# IntegratedSensor.net
KiCad netlist of a schematic drawn in EAGLE
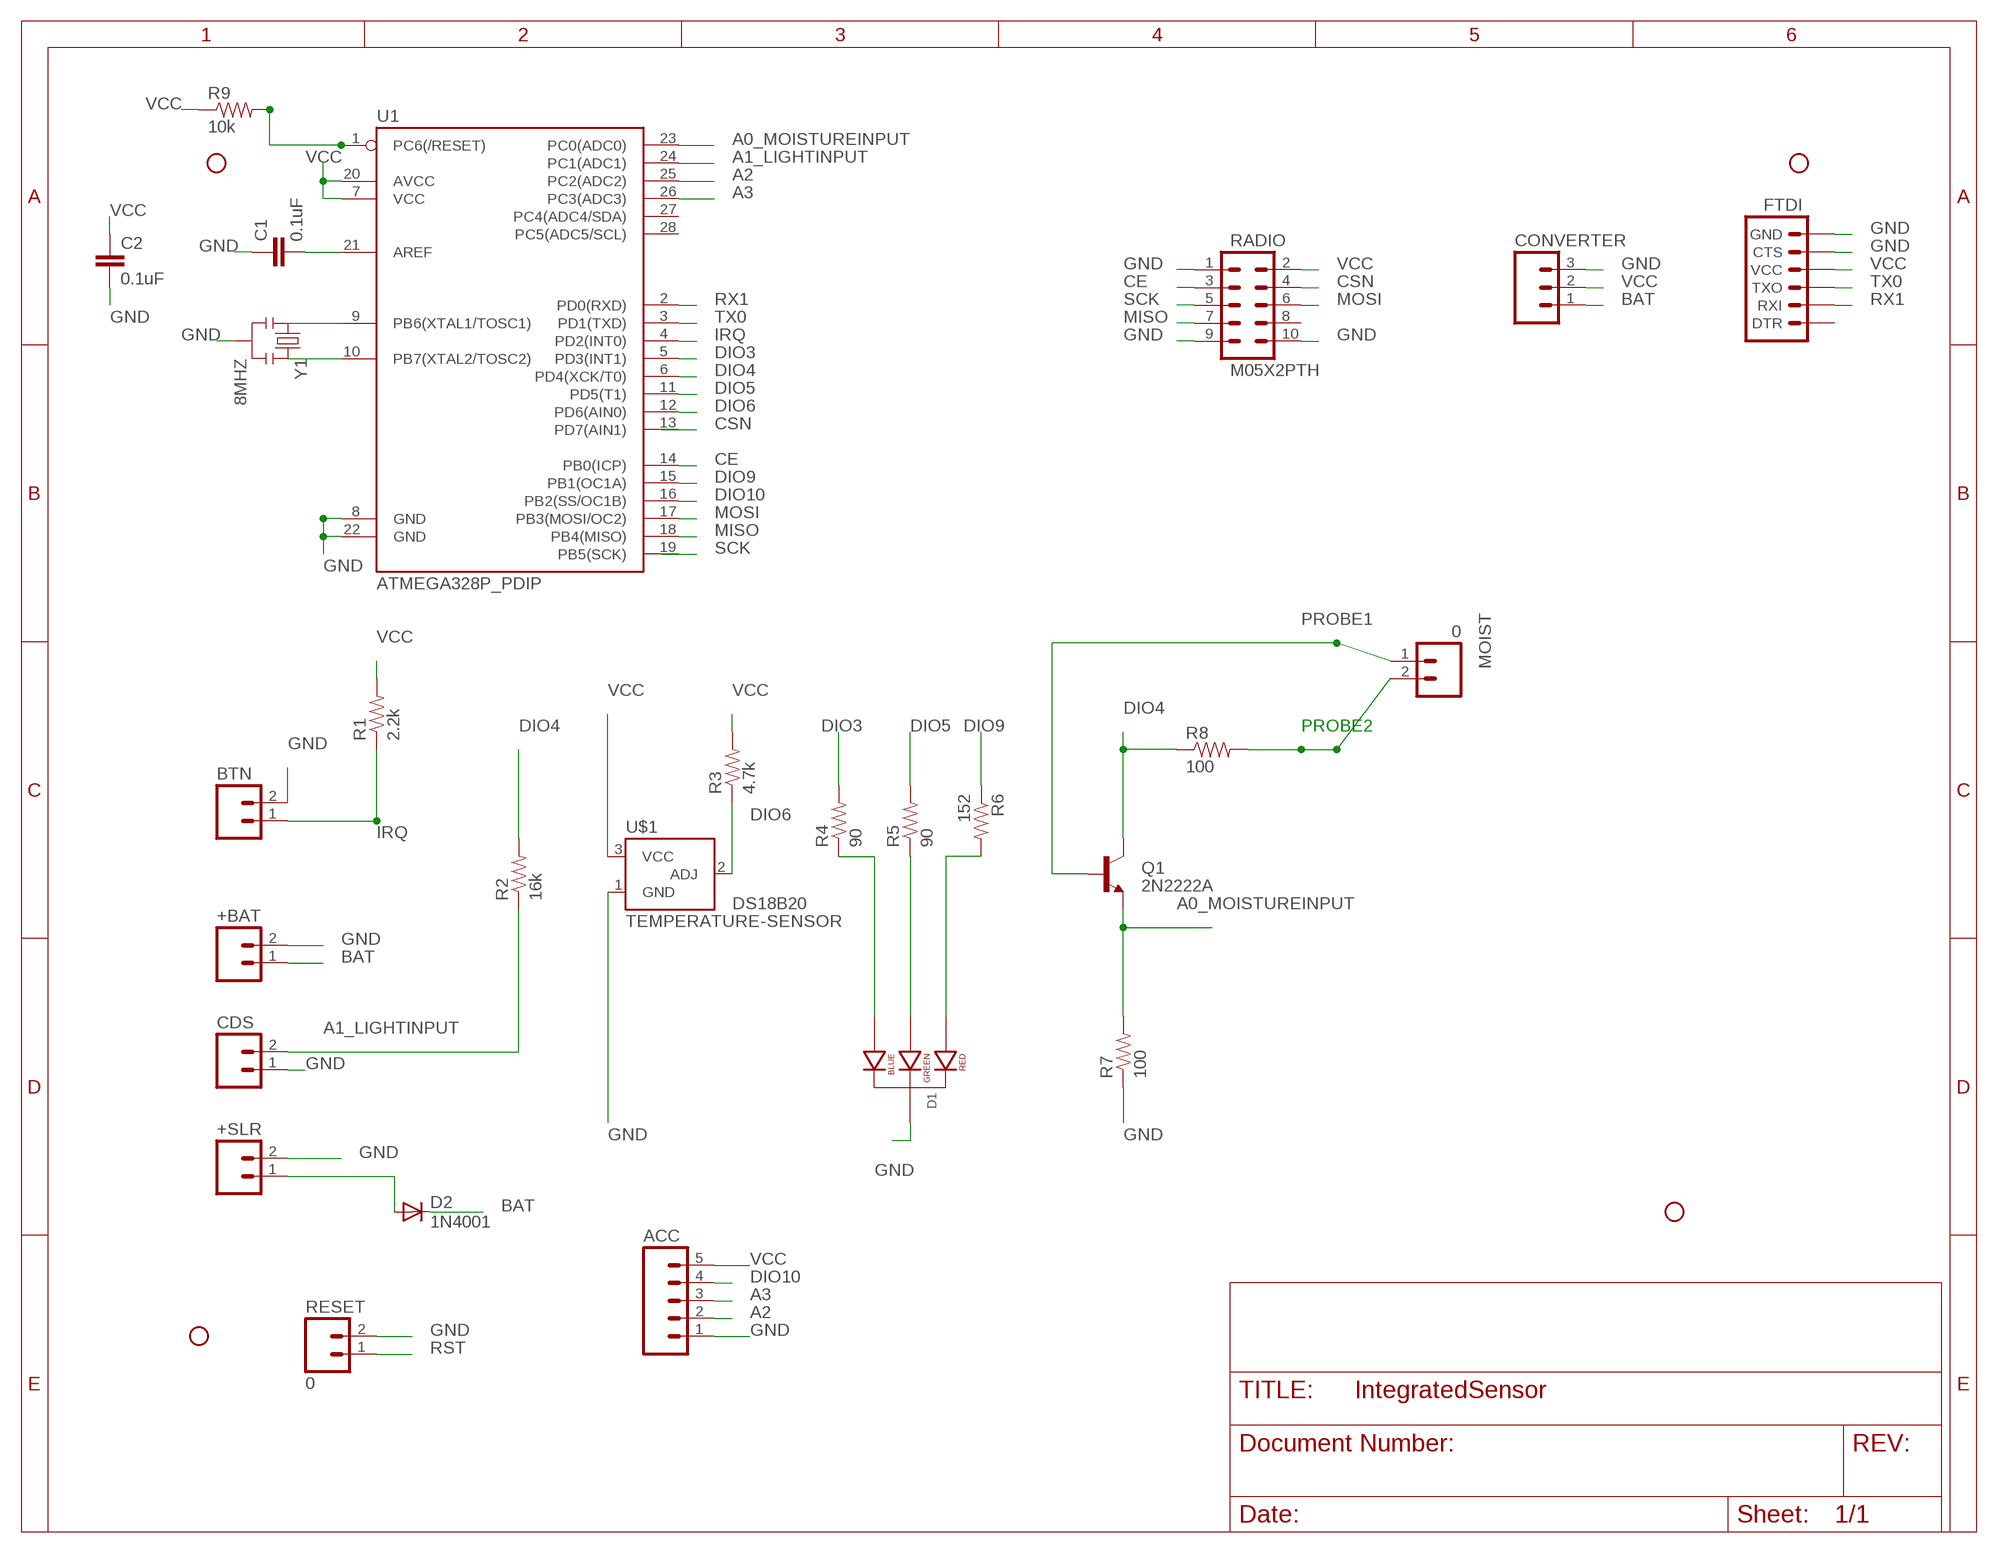
[diagram p0: schematic, sheet 1]

(export (version "E")
  (design (tool "Eeschema 10.0.6"))
  (components
    (comp (ref "+BAT")
      (value "M02PTH")
      (footprint "eagle-import:1X02")
      (libsource (lib "eagle-import") (part "M02PTH"))
    )
    (comp (ref "+SLR")
      (value "M02PTH")
      (footprint "eagle-import:1X02")
      (libsource (lib "eagle-import") (part "M02PTH"))
    )
    (comp (ref "ACC")
      (value "M05PTH")
      (footprint "eagle-import:1X05")
      (libsource (lib "eagle-import") (part "M05PTH"))
    )
    (comp (ref "BTN")
      (value "M02PTH")
      (footprint "eagle-import:1X02")
      (libsource (lib "eagle-import") (part "M02PTH"))
    )
    (comp (ref "C1")
      (value "0.1uF")
      (footprint "eagle-import:0402-CAP")
      (libsource (lib "eagle-import") (part "0.1UF-25V(+80/-20%)(0603)"))
    )
    (comp (ref "C2")
      (value "0.1uF")
      (footprint "eagle-import:0402-CAP")
      (libsource (lib "eagle-import") (part "0.1UF-25V(+80/-20%)(0603)"))
    )
    (comp (ref "CDS")
      (value "M02PTH")
      (footprint "eagle-import:1X02")
      (libsource (lib "eagle-import") (part "M02PTH"))
    )
    (comp (ref "CONVERTER")
      (value "M03PTH")
      (footprint "eagle-import:1X03")
      (libsource (lib "eagle-import") (part "M03PTH"))
    )
    (comp (ref "D1")
      (value "LED-RGB-CC-THRUCLEAR")
      (footprint "eagle-import:LED-RGB-THRU")
      (libsource (lib "eagle-import") (part "LED-RGB-CC-THRUCLEAR"))
    )
    (comp (ref "D2")
      (value "1N4001")
      (footprint "eagle-import:DIODE-1N4001")
      (libsource (lib "eagle-import") (part "DIODEPTH"))
    )
    (comp (ref "FTDI")
      (value "ARDUINO_SERIAL_PROGRAMPTH")
      (footprint "eagle-import:1X06")
      (libsource (lib "eagle-import") (part "ARDUINO_SERIAL_PROGRAMPTH"))
    )
    (comp (ref "MOIST")
      (value "0")
      (footprint "eagle-import:1X02")
      (libsource (lib "eagle-import") (part "M02PTH"))
    )
    (comp (ref "Q1")
      (value "2N2222A")
      (footprint "eagle-import:TO-92-AMMO")
      (libsource (lib "eagle-import") (part "TRANSISTOR_NPNTO-92-AMMO"))
    )
    (comp (ref "R1")
      (value "2.2k")
      (footprint "eagle-import:1_6W-RES")
      (libsource (lib "eagle-import") (part "RESISTORPTH-1/6W"))
    )
    (comp (ref "R2")
      (value "16k")
      (footprint "eagle-import:1_6W-RES")
      (libsource (lib "eagle-import") (part "RESISTORPTH-1/6W"))
    )
    (comp (ref "R3")
      (value "4.7k")
      (footprint "eagle-import:1_6W-RES")
      (libsource (lib "eagle-import") (part "RESISTORPTH-1/6W"))
    )
    (comp (ref "R4")
      (value "90")
      (footprint "eagle-import:1_6W-RES")
      (libsource (lib "eagle-import") (part "RESISTORPTH-1/6W"))
    )
    (comp (ref "R5")
      (value "90")
      (footprint "eagle-import:1_6W-RES")
      (libsource (lib "eagle-import") (part "RESISTORPTH-1/6W"))
    )
    (comp (ref "R6")
      (value "152")
      (footprint "eagle-import:1_6W-RES")
      (libsource (lib "eagle-import") (part "RESISTORPTH-1/6W"))
    )
    (comp (ref "R7")
      (value "100")
      (footprint "eagle-import:1_6W-RES")
      (libsource (lib "eagle-import") (part "RESISTORPTH-1/6W"))
    )
    (comp (ref "R8")
      (value "100")
      (footprint "eagle-import:1_6W-RES")
      (libsource (lib "eagle-import") (part "RESISTORPTH-1/6W"))
    )
    (comp (ref "R9")
      (value "10k")
      (footprint "eagle-import:1_6W-RES")
      (libsource (lib "eagle-import") (part "RESISTORPTH-1/6W"))
    )
    (comp (ref "RADIO")
      (value "M05X2PTH")
      (footprint "eagle-import:AVR_ICSP")
      (libsource (lib "eagle-import") (part "M05X2PTH"))
    )
    (comp (ref "RESET")
      (value "0")
      (footprint "eagle-import:1X02")
      (libsource (lib "eagle-import") (part "M02PTH"))
    )
    (comp (ref "STANDOFF1")
      (value "STAND-OFF")
      (footprint "eagle-import:STAND-OFF")
      (libsource (lib "eagle-import") (part "STAND-OFF"))
    )
    (comp (ref "STANDOFF2")
      (value "STAND-OFF")
      (footprint "eagle-import:STAND-OFF")
      (libsource (lib "eagle-import") (part "STAND-OFF"))
    )
    (comp (ref "STANDOFF3")
      (value "STAND-OFF")
      (footprint "eagle-import:STAND-OFF")
      (libsource (lib "eagle-import") (part "STAND-OFF"))
    )
    (comp (ref "STANDOFF4")
      (value "STAND-OFF")
      (footprint "eagle-import:STAND-OFF")
      (libsource (lib "eagle-import") (part "STAND-OFF"))
    )
    (comp (ref "U$1")
      (value "TEMPERATURE-SENSOR")
      (footprint "eagle-import:TO-92")
      (fields (field (name "PARTNAME") "DS18B20"))
      (libsource (lib "eagle-import") (part "TEMPERATURE-SENSOR"))
    )
    (comp (ref "U1")
      (value "ATMEGA328P_PDIP")
      (footprint "eagle-import:DIL28-3")
      (libsource (lib "eagle-import") (part "ATMEGA328P_PDIP"))
    )
    (comp (ref "Y1")
      (value "8MHZ")
      (footprint "eagle-import:RESONATOR-SMD")
      (libsource (lib "eagle-import") (part "RESONATOR8MHZ"))
    )
  )
  (nets
    (net (code "1") (name "/A0_MOISTUREINPUT") (class "Default")
      (node (ref "Q1") (pin "1") (pinfunction "E_1") (pintype "passive"))
      (node (ref "R7") (pin "2") (pinfunction "2_2") (pintype "passive"))
      (node (ref "U1") (pin "23") (pinfunction "PC0(ADC0)_23") (pintype "bidirectional"))
    )
    (net (code "2") (name "/A1_LIGHTINPUT") (class "Default")
      (node (ref "CDS") (pin "2") (pinfunction "2_2") (pintype "passive"))
      (node (ref "R2") (pin "1") (pinfunction "1_1") (pintype "passive"))
      (node (ref "U1") (pin "24") (pinfunction "PC1(ADC1)_24") (pintype "bidirectional"))
    )
    (net (code "3") (name "/A2") (class "Default")
      (node (ref "ACC") (pin "2") (pinfunction "2_2") (pintype "passive"))
      (node (ref "U1") (pin "25") (pinfunction "PC2(ADC2)_25") (pintype "bidirectional"))
    )
    (net (code "4") (name "/A3") (class "Default")
      (node (ref "ACC") (pin "3") (pinfunction "3_3") (pintype "passive"))
      (node (ref "U1") (pin "26") (pinfunction "PC3(ADC3)_26") (pintype "bidirectional"))
    )
    (net (code "5") (name "/BAT") (class "Default")
      (node (ref "+BAT") (pin "1") (pinfunction "1_1") (pintype "passive"))
      (node (ref "CONVERTER") (pin "1") (pinfunction "1_1") (pintype "passive"))
      (node (ref "D2") (pin "C") (pinfunction "C_C") (pintype "passive"))
    )
    (net (code "6") (name "/CE") (class "Default")
      (node (ref "RADIO") (pin "3") (pinfunction "3_3") (pintype "passive"))
      (node (ref "U1") (pin "14") (pinfunction "PB0(ICP)_14") (pintype "bidirectional"))
    )
    (net (code "7") (name "/CSN") (class "Default")
      (node (ref "RADIO") (pin "4") (pinfunction "4_4") (pintype "passive"))
    )
    (net (code "8") (name "/DIO3") (class "Default")
      (node (ref "R4") (pin "2") (pinfunction "2_2") (pintype "passive"))
      (node (ref "U1") (pin "5") (pinfunction "PD3(INT1)_5") (pintype "bidirectional"))
    )
    (net (code "9") (name "/DIO4") (class "Default")
      (node (ref "Q1") (pin "3") (pinfunction "C_3") (pintype "passive"))
      (node (ref "R2") (pin "2") (pinfunction "2_2") (pintype "passive"))
      (node (ref "R8") (pin "1") (pinfunction "1_1") (pintype "passive"))
      (node (ref "U1") (pin "6") (pinfunction "PD4(XCK/T0)_6") (pintype "bidirectional"))
    )
    (net (code "10") (name "/DIO5") (class "Default")
      (node (ref "R5") (pin "2") (pinfunction "2_2") (pintype "passive"))
      (node (ref "U1") (pin "11") (pinfunction "PD5(T1)_11") (pintype "bidirectional"))
    )
    (net (code "11") (name "/DIO6") (class "Default")
      (node (ref "R3") (pin "1") (pinfunction "1_1") (pintype "passive"))
      (node (ref "U$1") (pin "2") (pinfunction "ADJ_2") (pintype "bidirectional"))
      (node (ref "U1") (pin "12") (pinfunction "PD6(AIN0)_12") (pintype "bidirectional"))
    )
    (net (code "12") (name "/DIO9") (class "Default")
      (node (ref "R6") (pin "1") (pinfunction "1_1") (pintype "passive"))
      (node (ref "U1") (pin "15") (pinfunction "PB1(OC1A)_15") (pintype "bidirectional"))
    )
    (net (code "13") (name "/DIO10") (class "Default")
      (node (ref "ACC") (pin "4") (pinfunction "4_4") (pintype "passive"))
      (node (ref "U1") (pin "16") (pinfunction "PB2(SS/OC1B)_16") (pintype "bidirectional"))
    )
    (net (code "14") (name "/GND") (class "Default")
      (node (ref "+BAT") (pin "2") (pinfunction "2_2") (pintype "passive"))
      (node (ref "+SLR") (pin "2") (pinfunction "2_2") (pintype "passive"))
      (node (ref "ACC") (pin "1") (pinfunction "1_1") (pintype "passive"))
      (node (ref "BTN") (pin "2") (pinfunction "2_2") (pintype "passive"))
      (node (ref "C1") (pin "1") (pinfunction "1_1") (pintype "passive"))
      (node (ref "C2") (pin "2") (pinfunction "2_2") (pintype "passive"))
      (node (ref "CDS") (pin "1") (pinfunction "1_1") (pintype "passive"))
      (node (ref "CONVERTER") (pin "3") (pinfunction "3_3") (pintype "passive"))
      (node (ref "D1") (pin "2") (pinfunction "CATHODE_2") (pintype "bidirectional"))
      (node (ref "FTDI") (pin "5") (pinfunction "CTS_5") (pintype "passive"))
      (node (ref "FTDI") (pin "6") (pinfunction "GND_6") (pintype "passive"))
      (node (ref "R7") (pin "1") (pinfunction "1_1") (pintype "passive"))
      (node (ref "RADIO") (pin "1") (pinfunction "1_1") (pintype "passive"))
      (node (ref "RADIO") (pin "10") (pinfunction "10_10") (pintype "passive"))
      (node (ref "RADIO") (pin "9") (pinfunction "9_9") (pintype "passive"))
      (node (ref "RESET") (pin "2") (pinfunction "2_2") (pintype "passive"))
      (node (ref "U$1") (pin "1") (pinfunction "GND_1") (pintype "bidirectional"))
      (node (ref "U1") (pin "22") (pinfunction "GND_22") (pintype "bidirectional"))
      (node (ref "U1") (pin "8") (pinfunction "GND_8") (pintype "bidirectional"))
      (node (ref "Y1") (pin "2") (pinfunction "2_2") (pintype "passive"))
    )
    (net (code "15") (name "/IRQ") (class "Default")
      (node (ref "BTN") (pin "1") (pinfunction "1_1") (pintype "passive"))
      (node (ref "R1") (pin "1") (pinfunction "1_1") (pintype "passive"))
      (node (ref "U1") (pin "4") (pinfunction "PD2(INT0)_4") (pintype "bidirectional"))
    )
    (net (code "16") (name "/MISO") (class "Default")
      (node (ref "RADIO") (pin "7") (pinfunction "7_7") (pintype "passive"))
      (node (ref "U1") (pin "18") (pinfunction "PB4(MISO)_18") (pintype "bidirectional"))
    )
    (net (code "17") (name "/MOSI") (class "Default")
      (node (ref "RADIO") (pin "6") (pinfunction "6_6") (pintype "passive"))
      (node (ref "U1") (pin "17") (pinfunction "PB3(MOSI/OC2)_17") (pintype "bidirectional"))
    )
    (net (code "18") (name "/PROBE1") (class "Default")
      (node (ref "MOIST") (pin "1") (pinfunction "1_1") (pintype "passive"))
      (node (ref "Q1") (pin "2") (pinfunction "B_2") (pintype "passive"))
    )
    (net (code "19") (name "/PROBE2") (class "Default")
      (node (ref "MOIST") (pin "2") (pinfunction "2_2") (pintype "passive"))
      (node (ref "R8") (pin "2") (pinfunction "2_2") (pintype "passive"))
    )
    (net (code "20") (name "/RST") (class "Default")
      (node (ref "RESET") (pin "1") (pinfunction "1_1") (pintype "passive"))
    )
    (net (code "21") (name "/RX1") (class "Default")
      (node (ref "FTDI") (pin "2") (pinfunction "RXI_2") (pintype "passive"))
      (node (ref "U1") (pin "2") (pinfunction "PD0(RXD)_2") (pintype "bidirectional"))
    )
    (net (code "22") (name "/SCK") (class "Default")
      (node (ref "RADIO") (pin "5") (pinfunction "5_5") (pintype "passive"))
    )
    (net (code "23") (name "/TX0") (class "Default")
      (node (ref "FTDI") (pin "3") (pinfunction "TXO_3") (pintype "passive"))
      (node (ref "U1") (pin "3") (pinfunction "PD1(TXD)_3") (pintype "bidirectional"))
    )
    (net (code "24") (name "/VCC") (class "Default")
      (node (ref "ACC") (pin "5") (pinfunction "5_5") (pintype "passive"))
      (node (ref "C2") (pin "1") (pinfunction "1_1") (pintype "passive"))
      (node (ref "CONVERTER") (pin "2") (pinfunction "2_2") (pintype "passive"))
      (node (ref "FTDI") (pin "4") (pinfunction "VCC_4") (pintype "passive"))
      (node (ref "R1") (pin "2") (pinfunction "2_2") (pintype "passive"))
      (node (ref "R3") (pin "2") (pinfunction "2_2") (pintype "passive"))
      (node (ref "R9") (pin "1") (pinfunction "1_1") (pintype "passive"))
      (node (ref "RADIO") (pin "2") (pinfunction "2_2") (pintype "passive"))
      (node (ref "U$1") (pin "3") (pinfunction "VCC_3") (pintype "bidirectional"))
      (node (ref "U1") (pin "20") (pinfunction "AVCC_20") (pintype "bidirectional"))
      (node (ref "U1") (pin "7") (pinfunction "VCC_7") (pintype "bidirectional"))
    )
    (net (code "25") (name "Net-(+SLR-Pad1)") (class "Default")
      (node (ref "+SLR") (pin "1") (pinfunction "1_1") (pintype "passive"))
      (node (ref "D2") (pin "A") (pinfunction "A_A") (pintype "passive"))
    )
    (net (code "26") (name "Net-(D1-BLUE_CATHODE)") (class "Default")
      (node (ref "D1") (pin "4") (pinfunction "BLUE_CATHODE_4") (pintype "bidirectional"))
      (node (ref "R4") (pin "1") (pinfunction "1_1") (pintype "passive"))
    )
    (net (code "27") (name "Net-(D1-GREEN_CATHODE)") (class "Default")
      (node (ref "D1") (pin "3") (pinfunction "GREEN_CATHODE_3") (pintype "bidirectional"))
      (node (ref "R5") (pin "1") (pinfunction "1_1") (pintype "passive"))
    )
    (net (code "28") (name "Net-(D1-RED_CATHODE)") (class "Default")
      (node (ref "D1") (pin "1") (pinfunction "RED_CATHODE_1") (pintype "bidirectional"))
      (node (ref "R6") (pin "2") (pinfunction "2_2") (pintype "passive"))
    )
    (net (code "29") (name "Net-(U1-AREF)") (class "Default")
      (node (ref "C1") (pin "2") (pinfunction "2_2") (pintype "passive"))
      (node (ref "U1") (pin "21") (pinfunction "AREF_21") (pintype "bidirectional"))
    )
    (net (code "30") (name "Net-(U1-PB6(XTAL1{slash}TOSC1))") (class "Default")
      (node (ref "U1") (pin "9") (pinfunction "PB6(XTAL1/TOSC1)_9") (pintype "bidirectional"))
      (node (ref "Y1") (pin "1") (pinfunction "1_1") (pintype "passive"))
    )
    (net (code "31") (name "Net-(U1-PB7(XTAL2{slash}TOSC2))") (class "Default")
      (node (ref "U1") (pin "10") (pinfunction "PB7(XTAL2/TOSC2)_10") (pintype "bidirectional"))
      (node (ref "Y1") (pin "3") (pinfunction "3_3") (pintype "passive"))
    )
    (net (code "32") (name "Net-(U1-PC6({slash}RESET))") (class "Default")
      (node (ref "R9") (pin "2") (pinfunction "2_2") (pintype "passive"))
      (node (ref "U1") (pin "1") (pinfunction "PC6(/RESET)_1") (pintype "bidirectional"))
    )
    (net (code "33") (name "unconnected-(FTDI-DTR-Pad1)") (class "Default")
      (node (ref "FTDI") (pin "1") (pinfunction "DTR_1") (pintype "passive"))
    )
    (net (code "34") (name "unconnected-(RADIO-Pad8)") (class "Default")
      (node (ref "RADIO") (pin "8") (pinfunction "8_8") (pintype "passive"))
    )
    (net (code "35") (name "unconnected-(U1-PB5(SCK)-Pad19)") (class "Default")
      (node (ref "U1") (pin "19") (pinfunction "PB5(SCK)_19") (pintype "bidirectional"))
    )
    (net (code "36") (name "unconnected-(U1-PC4(ADC4{slash}SDA)-Pad27)") (class "Default")
      (node (ref "U1") (pin "27") (pinfunction "PC4(ADC4/SDA)_27") (pintype "bidirectional"))
    )
    (net (code "37") (name "unconnected-(U1-PC5(ADC5{slash}SCL)-Pad28)") (class "Default")
      (node (ref "U1") (pin "28") (pinfunction "PC5(ADC5/SCL)_28") (pintype "bidirectional"))
    )
    (net (code "38") (name "unconnected-(U1-PD7(AIN1)-Pad13)") (class "Default")
      (node (ref "U1") (pin "13") (pinfunction "PD7(AIN1)_13") (pintype "bidirectional"))
    )
  )
)
